# wifiToNmea2000.net
KiCad netlist of a schematic drawn in EAGLE
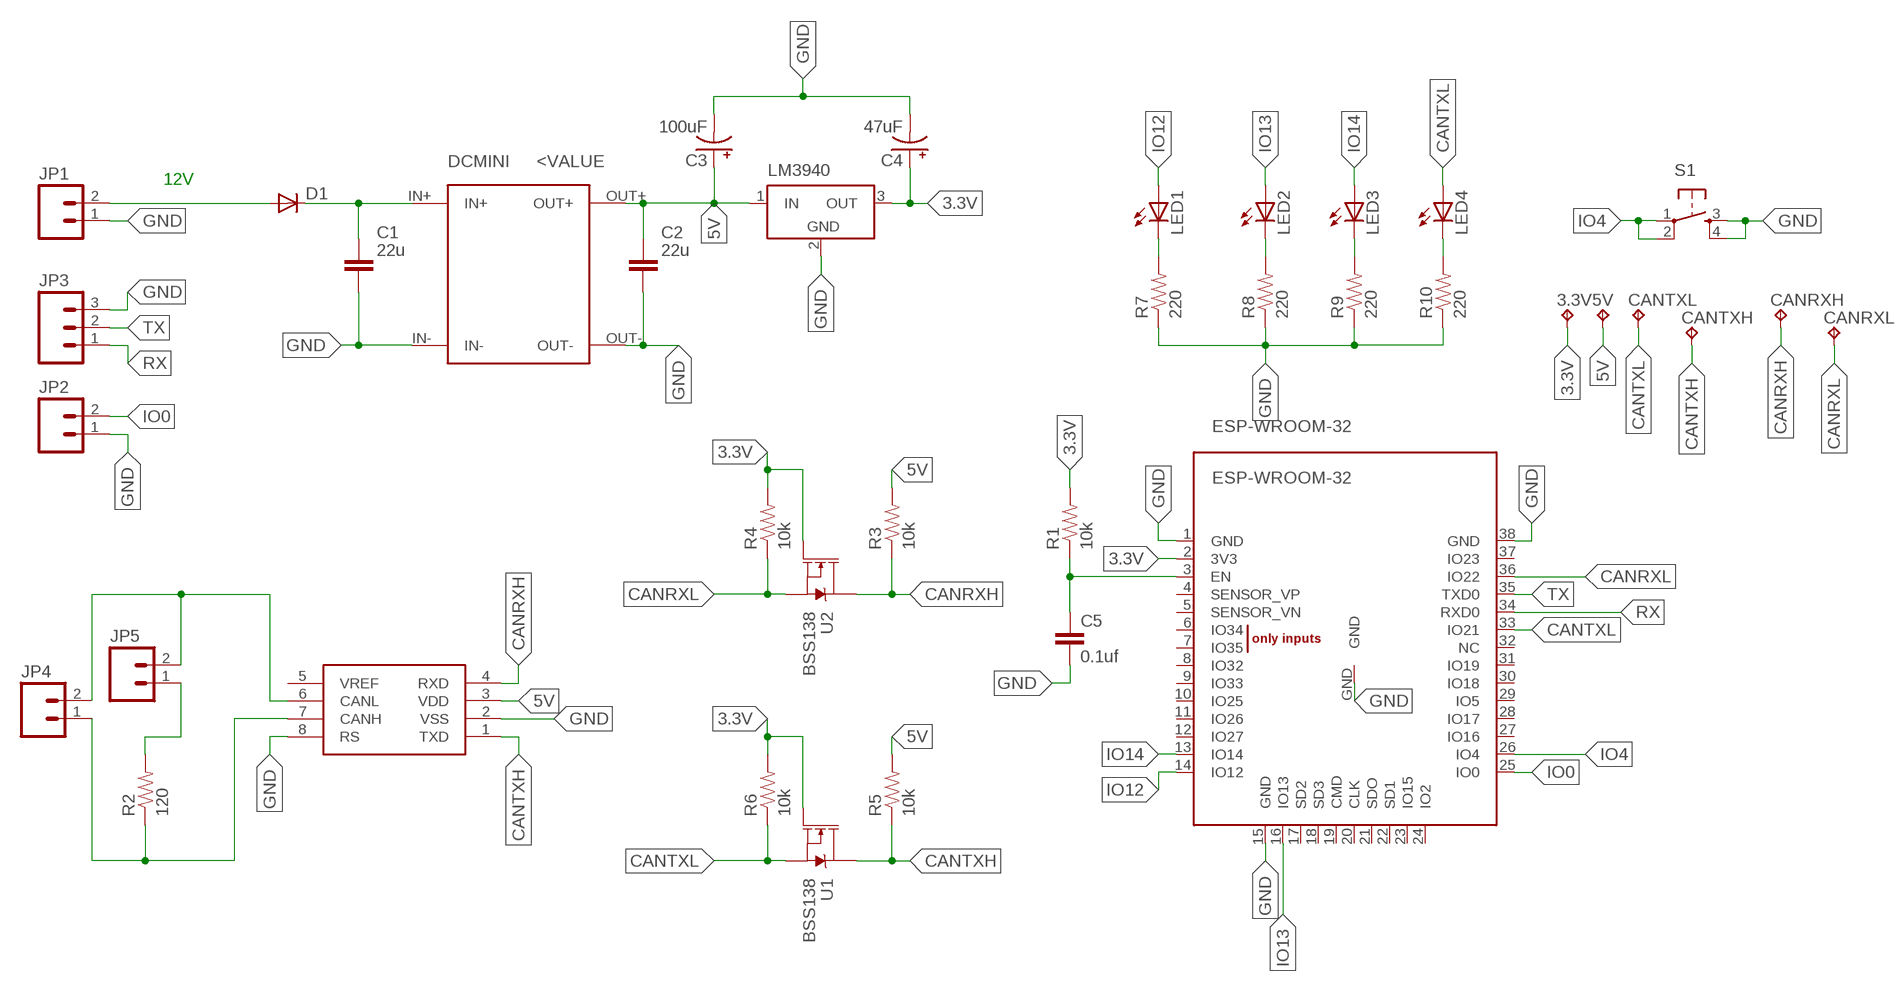
[diagram p0: schematic, sheet 1]

(export (version "E")
  (design (tool "Eeschema 10.0.6"))
  (components
    (comp (ref "3.3V")
      (value "TPTP20R")
      (footprint "eagle-import:TP20R")
      (libsource (lib "eagle-import") (part "TPTP20R"))
    )
    (comp (ref "5V")
      (value "TPTP20R")
      (footprint "eagle-import:TP20R")
      (libsource (lib "eagle-import") (part "TPTP20R"))
    )
    (comp (ref "C1")
      (value "22u")
      (footprint "eagle-import:C1206")
      (libsource (lib "eagle-import") (part "CAPACITOR_NPOL-1206"))
    )
    (comp (ref "C2")
      (value "22u")
      (footprint "eagle-import:C1206")
      (libsource (lib "eagle-import") (part "CAPACITOR_NPOL-1206"))
    )
    (comp (ref "C3")
      (value "100uF")
      (footprint "eagle-import:PANASONIC_D")
      (libsource (lib "eagle-import") (part "CAP_POLD"))
    )
    (comp (ref "C4")
      (value "47uF")
      (footprint "eagle-import:PANASONIC_D")
      (libsource (lib "eagle-import") (part "CAP_POLD"))
    )
    (comp (ref "C5")
      (value "0.1uf")
      (footprint "eagle-import:0805")
      (libsource (lib "eagle-import") (part "CAP0805"))
    )
    (comp (ref "CANRXH")
      (value "TPTP20R")
      (footprint "eagle-import:TP20R")
      (libsource (lib "eagle-import") (part "TPTP20R"))
    )
    (comp (ref "CANRXL")
      (value "TPTP20R")
      (footprint "eagle-import:TP20R")
      (libsource (lib "eagle-import") (part "TPTP20R"))
    )
    (comp (ref "CANTXH")
      (value "TPTP20R")
      (footprint "eagle-import:TP20R")
      (libsource (lib "eagle-import") (part "TPTP20R"))
    )
    (comp (ref "CANTXL")
      (value "TPTP20R")
      (footprint "eagle-import:TP20R")
      (libsource (lib "eagle-import") (part "TPTP20R"))
    )
    (comp (ref "D1")
      (value "DIODE-DO214AC")
      (footprint "eagle-import:DO214AC")
      (libsource (lib "eagle-import") (part "DIODE-DO214AC"))
    )
    (comp (ref "DCMINI")
      (value "DCDCMINI")
      (footprint "eagle-import:DCDCMINI")
      (libsource (lib "eagle-import") (part "DCDCMINI"))
    )
    (comp (ref "ESP-WROOM-32")
      (value "ESP-WROOM-32")
      (footprint "eagle-import:ESP-WROOM-32")
      (libsource (lib "eagle-import") (part "ESP-WROOM-32"))
    )
    (comp (ref "JP1")
      (value "M02")
      (footprint "eagle-import:1X02_LONGPADS")
      (libsource (lib "eagle-import") (part "M02"))
    )
    (comp (ref "JP2")
      (value "M02LOCK")
      (footprint "eagle-import:1X02_LOCK")
      (libsource (lib "eagle-import") (part "M02LOCK"))
    )
    (comp (ref "JP3")
      (value "M03LOCK")
      (footprint "eagle-import:1X03_LOCK")
      (libsource (lib "eagle-import") (part "M03LOCK"))
    )
    (comp (ref "JP4")
      (value "M02")
      (footprint "eagle-import:1X02_LONGPADS")
      (libsource (lib "eagle-import") (part "M02"))
    )
    (comp (ref "JP5")
      (value "M02LOCK")
      (footprint "eagle-import:1X02_LOCK")
      (libsource (lib "eagle-import") (part "M02LOCK"))
    )
    (comp (ref "LED1")
      (value "LED3MM")
      (footprint "eagle-import:LED3MM")
      (libsource (lib "eagle-import") (part "LED3MM"))
    )
    (comp (ref "LED2")
      (value "LED3MM")
      (footprint "eagle-import:LED3MM")
      (libsource (lib "eagle-import") (part "LED3MM"))
    )
    (comp (ref "LED3")
      (value "LED3MM")
      (footprint "eagle-import:LED3MM")
      (libsource (lib "eagle-import") (part "LED3MM"))
    )
    (comp (ref "LED4")
      (value "LED3MM")
      (footprint "eagle-import:LED3MM")
      (libsource (lib "eagle-import") (part "LED3MM"))
    )
    (comp (ref "LM3940")
      (value "LT1129CST5")
      (footprint "eagle-import:SOT223")
      (libsource (lib "eagle-import") (part "LT1129CST5"))
    )
    (comp (ref "MCP2551")
      (value "MCP2551")
      (footprint "eagle-import:SO08")
      (libsource (lib "eagle-import") (part "MCP2551"))
    )
    (comp (ref "R1")
      (value "10k")
      (footprint "eagle-import:0805")
      (libsource (lib "eagle-import") (part "RESISTOR"))
    )
    (comp (ref "R2")
      (value "120")
      (footprint "eagle-import:0805")
      (libsource (lib "eagle-import") (part "RESISTOR"))
    )
    (comp (ref "R3")
      (value "10k")
      (footprint "eagle-import:0805")
      (libsource (lib "eagle-import") (part "RESISTOR"))
    )
    (comp (ref "R4")
      (value "10k")
      (footprint "eagle-import:0805")
      (libsource (lib "eagle-import") (part "RESISTOR"))
    )
    (comp (ref "R5")
      (value "10k")
      (footprint "eagle-import:0805")
      (libsource (lib "eagle-import") (part "RESISTOR"))
    )
    (comp (ref "R6")
      (value "10k")
      (footprint "eagle-import:0805")
      (libsource (lib "eagle-import") (part "RESISTOR"))
    )
    (comp (ref "R7")
      (value "220")
      (footprint "eagle-import:0805")
      (libsource (lib "eagle-import") (part "RESISTOR"))
    )
    (comp (ref "R8")
      (value "220")
      (footprint "eagle-import:0805")
      (libsource (lib "eagle-import") (part "RESISTOR"))
    )
    (comp (ref "R9")
      (value "220")
      (footprint "eagle-import:0805")
      (libsource (lib "eagle-import") (part "RESISTOR"))
    )
    (comp (ref "R10")
      (value "220")
      (footprint "eagle-import:0805")
      (libsource (lib "eagle-import") (part "RESISTOR"))
    )
    (comp (ref "S1")
      (value "TAC_SWITCHPTH")
      (footprint "eagle-import:TACTILE-PTH")
      (libsource (lib "eagle-import") (part "TAC_SWITCHPTH"))
    )
    (comp (ref "U1")
      (value "BSS138")
      (footprint "eagle-import:SOT65P210X110-3N")
      (fields (field (name "MPN") "BSS138BKW"))
      (libsource (lib "eagle-import") (part "BSS138BKW"))
    )
    (comp (ref "U2")
      (value "BSS138")
      (footprint "eagle-import:SOT65P210X110-3N")
      (fields (field (name "MPN") "BSS138BKW"))
      (libsource (lib "eagle-import") (part "BSS138BKW"))
    )
  )
  (nets
    (net (code "1") (name "3.3V") (class "Default")
      (node (ref "3.3V") (pin "TP") (pinfunction "TP_TP") (pintype "input"))
      (node (ref "C4") (pin "+") (pinfunction "+_+") (pintype "passive"))
      (node (ref "ESP-WROOM-32") (pin "2") (pinfunction "3V3_2") (pintype "bidirectional"))
      (node (ref "LM3940") (pin "3") (pinfunction "OUT_3") (pintype "output"))
      (node (ref "R1") (pin "2") (pinfunction "2_2") (pintype "passive"))
      (node (ref "R4") (pin "2") (pinfunction "2_2") (pintype "passive"))
      (node (ref "R6") (pin "2") (pinfunction "2_2") (pintype "passive"))
      (node (ref "U1") (pin "1") (pinfunction "G_1") (pintype "bidirectional"))
      (node (ref "U2") (pin "1") (pinfunction "G_1") (pintype "bidirectional"))
    )
    (net (code "2") (name "5V") (class "Default")
      (node (ref "5V") (pin "TP") (pinfunction "TP_TP") (pintype "input"))
      (node (ref "C2") (pin "1") (pinfunction "1_1") (pintype "passive"))
      (node (ref "C3") (pin "+") (pinfunction "+_+") (pintype "passive"))
      (node (ref "DCMINI") (pin "OUT+") (pinfunction "OUT+_OUT+") (pintype "bidirectional"))
      (node (ref "LM3940") (pin "1") (pinfunction "IN_1") (pintype "input"))
      (node (ref "MCP2551") (pin "3") (pinfunction "VDD_3") (pintype "bidirectional"))
      (node (ref "R3") (pin "2") (pinfunction "2_2") (pintype "passive"))
      (node (ref "R5") (pin "2") (pinfunction "2_2") (pintype "passive"))
    )
    (net (code "3") (name "CANRXH") (class "Default")
      (node (ref "CANRXH") (pin "TP") (pinfunction "TP_TP") (pintype "input"))
      (node (ref "MCP2551") (pin "4") (pinfunction "RXD_4") (pintype "bidirectional"))
      (node (ref "R3") (pin "1") (pinfunction "1_1") (pintype "passive"))
      (node (ref "U2") (pin "3") (pinfunction "D_3") (pintype "bidirectional"))
    )
    (net (code "4") (name "CANRXL") (class "Default")
      (node (ref "CANRXL") (pin "TP") (pinfunction "TP_TP") (pintype "input"))
      (node (ref "ESP-WROOM-32") (pin "36") (pinfunction "IO22_36") (pintype "bidirectional"))
      (node (ref "R4") (pin "1") (pinfunction "1_1") (pintype "passive"))
      (node (ref "U2") (pin "2") (pinfunction "S_2") (pintype "bidirectional"))
    )
    (net (code "5") (name "CANTXH") (class "Default")
      (node (ref "CANTXH") (pin "TP") (pinfunction "TP_TP") (pintype "input"))
      (node (ref "MCP2551") (pin "1") (pinfunction "TXD_1") (pintype "bidirectional"))
      (node (ref "R5") (pin "1") (pinfunction "1_1") (pintype "passive"))
      (node (ref "U1") (pin "3") (pinfunction "D_3") (pintype "bidirectional"))
    )
    (net (code "6") (name "CANTXL") (class "Default")
      (node (ref "CANTXL") (pin "TP") (pinfunction "TP_TP") (pintype "input"))
      (node (ref "ESP-WROOM-32") (pin "33") (pinfunction "IO21_33") (pintype "bidirectional"))
      (node (ref "LED4") (pin "A") (pinfunction "A_A") (pintype "passive"))
      (node (ref "R6") (pin "1") (pinfunction "1_1") (pintype "passive"))
      (node (ref "U1") (pin "2") (pinfunction "S_2") (pintype "bidirectional"))
    )
    (net (code "7") (name "GND") (class "Default")
      (node (ref "C1") (pin "2") (pinfunction "2_2") (pintype "passive"))
      (node (ref "C2") (pin "2") (pinfunction "2_2") (pintype "passive"))
      (node (ref "C3") (pin "-") (pinfunction "-_-") (pintype "passive"))
      (node (ref "C4") (pin "-") (pinfunction "-_-") (pintype "passive"))
      (node (ref "C5") (pin "2") (pinfunction "2_2") (pintype "passive"))
      (node (ref "DCMINI") (pin "IN-") (pinfunction "IN-_IN-") (pintype "bidirectional"))
      (node (ref "DCMINI") (pin "OUT-") (pinfunction "OUT-_OUT-") (pintype "bidirectional"))
      (node (ref "ESP-WROOM-32") (pin "1") (pinfunction "GND_1") (pintype "bidirectional"))
      (node (ref "ESP-WROOM-32") (pin "15") (pinfunction "GND_15") (pintype "bidirectional"))
      (node (ref "ESP-WROOM-32") (pin "38") (pinfunction "GND_38") (pintype "bidirectional"))
      (node (ref "ESP-WROOM-32") (pin "GND") (pinfunction "GND_GND") (pintype "bidirectional"))
      (node (ref "JP1") (pin "1") (pinfunction "1_1") (pintype "passive"))
      (node (ref "JP2") (pin "1") (pinfunction "1_1") (pintype "passive"))
      (node (ref "JP3") (pin "3") (pinfunction "3_3") (pintype "passive"))
      (node (ref "LM3940") (pin "2") (pinfunction "GND_2") (pintype "power_in"))
      (node (ref "MCP2551") (pin "2") (pinfunction "VSS_2") (pintype "bidirectional"))
      (node (ref "MCP2551") (pin "8") (pinfunction "RS_8") (pintype "bidirectional"))
      (node (ref "R10") (pin "1") (pinfunction "1_1") (pintype "passive"))
      (node (ref "R7") (pin "1") (pinfunction "1_1") (pintype "passive"))
      (node (ref "R8") (pin "1") (pinfunction "1_1") (pintype "passive"))
      (node (ref "R9") (pin "1") (pinfunction "1_1") (pintype "passive"))
      (node (ref "S1") (pin "3") (pinfunction "3_3") (pintype "passive"))
      (node (ref "S1") (pin "4") (pinfunction "4_4") (pintype "passive"))
    )
    (net (code "8") (name "IO0") (class "Default")
      (node (ref "ESP-WROOM-32") (pin "25") (pinfunction "IO0_25") (pintype "bidirectional"))
      (node (ref "JP2") (pin "2") (pinfunction "2_2") (pintype "passive"))
    )
    (net (code "9") (name "IO4") (class "Default")
      (node (ref "ESP-WROOM-32") (pin "26") (pinfunction "IO4_26") (pintype "bidirectional"))
      (node (ref "S1") (pin "1") (pinfunction "1_1") (pintype "passive"))
      (node (ref "S1") (pin "2") (pinfunction "2_2") (pintype "passive"))
    )
    (net (code "10") (name "IO12") (class "Default")
      (node (ref "ESP-WROOM-32") (pin "14") (pinfunction "IO12_14") (pintype "bidirectional"))
      (node (ref "LED1") (pin "A") (pinfunction "A_A") (pintype "passive"))
    )
    (net (code "11") (name "IO13") (class "Default")
      (node (ref "ESP-WROOM-32") (pin "16") (pinfunction "IO13_16") (pintype "bidirectional"))
      (node (ref "LED2") (pin "A") (pinfunction "A_A") (pintype "passive"))
    )
    (net (code "12") (name "IO14") (class "Default")
      (node (ref "ESP-WROOM-32") (pin "13") (pinfunction "IO14_13") (pintype "bidirectional"))
      (node (ref "LED3") (pin "A") (pinfunction "A_A") (pintype "passive"))
    )
    (net (code "13") (name "Net-(C1-Pad1)") (class "Default")
      (node (ref "C1") (pin "1") (pinfunction "1_1") (pintype "passive"))
      (node (ref "D1") (pin "C") (pinfunction "C_C") (pintype "passive"))
      (node (ref "DCMINI") (pin "IN+") (pinfunction "IN+_IN+") (pintype "bidirectional"))
    )
    (net (code "14") (name "Net-(D1-PadA)") (class "Default")
      (node (ref "D1") (pin "A") (pinfunction "A_A") (pintype "passive"))
      (node (ref "JP1") (pin "2") (pinfunction "2_2") (pintype "passive"))
    )
    (net (code "15") (name "Net-(ESP-WROOM-32-EN)") (class "Default")
      (node (ref "C5") (pin "1") (pinfunction "1_1") (pintype "passive"))
      (node (ref "ESP-WROOM-32") (pin "3") (pinfunction "EN_3") (pintype "bidirectional"))
      (node (ref "R1") (pin "1") (pinfunction "1_1") (pintype "passive"))
    )
    (net (code "16") (name "Net-(JP5-Pad1)") (class "Default")
      (node (ref "JP5") (pin "1") (pinfunction "1_1") (pintype "passive"))
      (node (ref "R2") (pin "2") (pinfunction "2_2") (pintype "passive"))
    )
    (net (code "17") (name "Net-(LED1-C)") (class "Default")
      (node (ref "LED1") (pin "K") (pinfunction "C_K") (pintype "passive"))
      (node (ref "R7") (pin "2") (pinfunction "2_2") (pintype "passive"))
    )
    (net (code "18") (name "Net-(LED2-C)") (class "Default")
      (node (ref "LED2") (pin "K") (pinfunction "C_K") (pintype "passive"))
      (node (ref "R8") (pin "2") (pinfunction "2_2") (pintype "passive"))
    )
    (net (code "19") (name "Net-(LED3-C)") (class "Default")
      (node (ref "LED3") (pin "K") (pinfunction "C_K") (pintype "passive"))
      (node (ref "R9") (pin "2") (pinfunction "2_2") (pintype "passive"))
    )
    (net (code "20") (name "Net-(LED4-C)") (class "Default")
      (node (ref "LED4") (pin "K") (pinfunction "C_K") (pintype "passive"))
      (node (ref "R10") (pin "2") (pinfunction "2_2") (pintype "passive"))
    )
    (net (code "21") (name "Net-(MCP2551-CANH)") (class "Default")
      (node (ref "JP4") (pin "1") (pinfunction "1_1") (pintype "passive"))
      (node (ref "MCP2551") (pin "7") (pinfunction "CANH_7") (pintype "bidirectional"))
      (node (ref "R2") (pin "1") (pinfunction "1_1") (pintype "passive"))
    )
    (net (code "22") (name "Net-(MCP2551-CANL)") (class "Default")
      (node (ref "JP4") (pin "2") (pinfunction "2_2") (pintype "passive"))
      (node (ref "JP5") (pin "2") (pinfunction "2_2") (pintype "passive"))
      (node (ref "MCP2551") (pin "6") (pinfunction "CANL_6") (pintype "bidirectional"))
    )
    (net (code "23") (name "RX") (class "Default")
      (node (ref "ESP-WROOM-32") (pin "34") (pinfunction "RXD0_34") (pintype "bidirectional"))
      (node (ref "JP3") (pin "1") (pinfunction "1_1") (pintype "passive"))
    )
    (net (code "24") (name "TX") (class "Default")
      (node (ref "ESP-WROOM-32") (pin "35") (pinfunction "TXD0_35") (pintype "bidirectional"))
      (node (ref "JP3") (pin "2") (pinfunction "2_2") (pintype "passive"))
    )
    (net (code "25") (name "unconnected-(ESP-WROOM-32-CLK-Pad20)") (class "Default")
      (node (ref "ESP-WROOM-32") (pin "20") (pinfunction "CLK_20") (pintype "bidirectional"))
    )
    (net (code "26") (name "unconnected-(ESP-WROOM-32-CMD-Pad19)") (class "Default")
      (node (ref "ESP-WROOM-32") (pin "19") (pinfunction "CMD_19") (pintype "bidirectional"))
    )
    (net (code "27") (name "unconnected-(ESP-WROOM-32-IO2-Pad24)") (class "Default")
      (node (ref "ESP-WROOM-32") (pin "24") (pinfunction "IO2_24") (pintype "bidirectional"))
    )
    (net (code "28") (name "unconnected-(ESP-WROOM-32-IO5-Pad29)") (class "Default")
      (node (ref "ESP-WROOM-32") (pin "29") (pinfunction "IO5_29") (pintype "bidirectional"))
    )
    (net (code "29") (name "unconnected-(ESP-WROOM-32-IO15-Pad23)") (class "Default")
      (node (ref "ESP-WROOM-32") (pin "23") (pinfunction "IO15_23") (pintype "bidirectional"))
    )
    (net (code "30") (name "unconnected-(ESP-WROOM-32-IO16-Pad27)") (class "Default")
      (node (ref "ESP-WROOM-32") (pin "27") (pinfunction "IO16_27") (pintype "bidirectional"))
    )
    (net (code "31") (name "unconnected-(ESP-WROOM-32-IO17-Pad28)") (class "Default")
      (node (ref "ESP-WROOM-32") (pin "28") (pinfunction "IO17_28") (pintype "bidirectional"))
    )
    (net (code "32") (name "unconnected-(ESP-WROOM-32-IO18-Pad30)") (class "Default")
      (node (ref "ESP-WROOM-32") (pin "30") (pinfunction "IO18_30") (pintype "bidirectional"))
    )
    (net (code "33") (name "unconnected-(ESP-WROOM-32-IO19-Pad31)") (class "Default")
      (node (ref "ESP-WROOM-32") (pin "31") (pinfunction "IO19_31") (pintype "bidirectional"))
    )
    (net (code "34") (name "unconnected-(ESP-WROOM-32-IO23-Pad37)") (class "Default")
      (node (ref "ESP-WROOM-32") (pin "37") (pinfunction "IO23_37") (pintype "bidirectional"))
    )
    (net (code "35") (name "unconnected-(ESP-WROOM-32-IO25-Pad10)") (class "Default")
      (node (ref "ESP-WROOM-32") (pin "10") (pinfunction "IO25_10") (pintype "bidirectional"))
    )
    (net (code "36") (name "unconnected-(ESP-WROOM-32-IO26-Pad11)") (class "Default")
      (node (ref "ESP-WROOM-32") (pin "11") (pinfunction "IO26_11") (pintype "bidirectional"))
    )
    (net (code "37") (name "unconnected-(ESP-WROOM-32-IO27-Pad12)") (class "Default")
      (node (ref "ESP-WROOM-32") (pin "12") (pinfunction "IO27_12") (pintype "bidirectional"))
    )
    (net (code "38") (name "unconnected-(ESP-WROOM-32-IO32-Pad8)") (class "Default")
      (node (ref "ESP-WROOM-32") (pin "8") (pinfunction "IO32_8") (pintype "bidirectional"))
    )
    (net (code "39") (name "unconnected-(ESP-WROOM-32-IO33-Pad9)") (class "Default")
      (node (ref "ESP-WROOM-32") (pin "9") (pinfunction "IO33_9") (pintype "bidirectional"))
    )
    (net (code "40") (name "unconnected-(ESP-WROOM-32-IO34-Pad6)") (class "Default")
      (node (ref "ESP-WROOM-32") (pin "6") (pinfunction "IO34_6") (pintype "input"))
    )
    (net (code "41") (name "unconnected-(ESP-WROOM-32-IO35-Pad7)") (class "Default")
      (node (ref "ESP-WROOM-32") (pin "7") (pinfunction "IO35_7") (pintype "input"))
    )
    (net (code "42") (name "unconnected-(ESP-WROOM-32-NC-Pad32)") (class "Default")
      (node (ref "ESP-WROOM-32") (pin "32") (pinfunction "NC_32") (pintype "bidirectional"))
    )
    (net (code "43") (name "unconnected-(ESP-WROOM-32-SD1-Pad22)") (class "Default")
      (node (ref "ESP-WROOM-32") (pin "22") (pinfunction "SD1_22") (pintype "bidirectional"))
    )
    (net (code "44") (name "unconnected-(ESP-WROOM-32-SD2-Pad17)") (class "Default")
      (node (ref "ESP-WROOM-32") (pin "17") (pinfunction "SD2_17") (pintype "bidirectional"))
    )
    (net (code "45") (name "unconnected-(ESP-WROOM-32-SD3-Pad18)") (class "Default")
      (node (ref "ESP-WROOM-32") (pin "18") (pinfunction "SD3_18") (pintype "bidirectional"))
    )
    (net (code "46") (name "unconnected-(ESP-WROOM-32-SDO-Pad21)") (class "Default")
      (node (ref "ESP-WROOM-32") (pin "21") (pinfunction "SDO_21") (pintype "bidirectional"))
    )
    (net (code "47") (name "unconnected-(ESP-WROOM-32-SENSOR_VN-Pad5)") (class "Default")
      (node (ref "ESP-WROOM-32") (pin "5") (pinfunction "SENSOR_VN_5") (pintype "input"))
    )
    (net (code "48") (name "unconnected-(ESP-WROOM-32-SENSOR_VP-Pad4)") (class "Default")
      (node (ref "ESP-WROOM-32") (pin "4") (pinfunction "SENSOR_VP_4") (pintype "input"))
    )
    (net (code "49") (name "unconnected-(MCP2551-VREF-Pad5)") (class "Default")
      (node (ref "MCP2551") (pin "5") (pinfunction "VREF_5") (pintype "bidirectional"))
    )
  )
)
